# com.net
KiCad netlist of a schematic drawn in Altium Designer
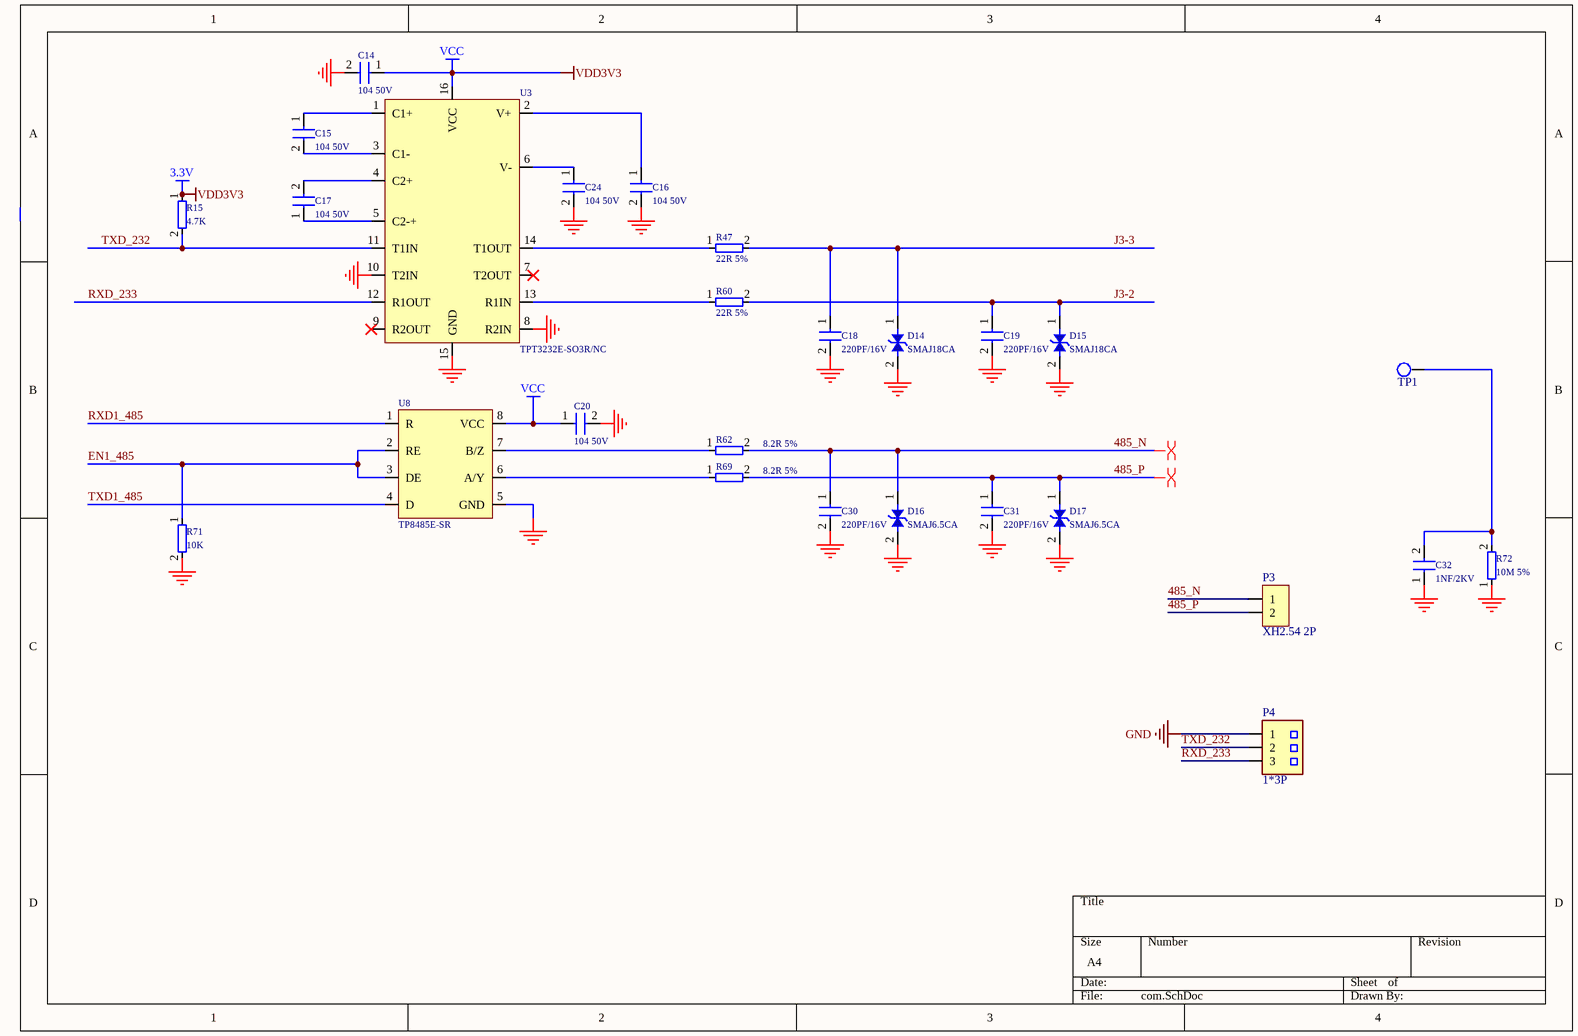
[diagram p0: com.SchDoc]

(export (version "E")
  (design (tool "Eeschema 10.0.6"))
  (components
    (comp (ref "C14") (value "104 50V") (footprint "0603C") (libsource (lib "*") (part "CAP")))
    (comp (ref "C15") (value "104 50V") (footprint "0603C") (libsource (lib "*") (part "CAP")))
    (comp (ref "C16") (value "104 50V") (footprint "0603C") (libsource (lib "*") (part "CAP")))
    (comp (ref "C17") (value "104 50V") (footprint "0603C") (libsource (lib "*") (part "CAP")))
    (comp (ref "C18") (value "220PF/16V") (footprint "0603C") (libsource (lib "*") (part "CAP")))
    (comp (ref "C19") (value "220PF/16V") (footprint "0603C") (libsource (lib "*") (part "CAP")))
    (comp (ref "C20") (value "104 50V") (footprint "0603C") (libsource (lib "*") (part "CAP")))
    (comp (ref "C24") (value "104 50V") (footprint "0603C") (libsource (lib "*") (part "CAP")))
    (comp (ref "C30") (value "220PF/16V") (footprint "0603C") (libsource (lib "*") (part "CAP")))
    (comp (ref "C31") (value "220PF/16V") (footprint "0603C") (libsource (lib "*") (part "CAP")))
    (comp (ref "C32") (value "1NF/2KV") (footprint "1206C") (libsource (lib "*") (part "CAP")))
    (comp (ref "D14") (value "SMAJ18CA") (footprint "SMA") (libsource (lib "*") (part "D_ESD")))
    (comp (ref "D15") (value "SMAJ18CA") (footprint "SMA") (libsource (lib "*") (part "D_ESD")))
    (comp (ref "D16") (value "SMAJ6.5CA") (footprint "SMA") (libsource (lib "*") (part "D_ESD")))
    (comp (ref "D17") (value "SMAJ6.5CA") (footprint "SMA") (libsource (lib "*") (part "D_ESD")))
    (comp (ref "P3")
      (value "XH2.54 2P")
      (footprint "SIP-2A")
      (description "XH2.54 2P 直插")
      (libsource (lib "XiaoyI") (part "SIP-2"))
    )
    (comp (ref "P4") (value "1*3P") (footprint "3X2.54MMZ2") (libsource (lib "PARK-N5 V1.0") (part "HDR1*3")))
    (comp (ref "R15") (value "4.7K") (footprint "0603R") (libsource (lib "*") (part "RES")))
    (comp (ref "R47") (value "22R 5%") (footprint "0603R") (libsource (lib "*") (part "RES")))
    (comp (ref "R60") (value "22R 5%") (footprint "0603R") (libsource (lib "*") (part "RES")))
    (comp (ref "R62") (value "8.2R 5%") (footprint "0603R") (libsource (lib "*") (part "RES")))
    (comp (ref "R69") (value "8.2R 5%") (footprint "0603R") (libsource (lib "*") (part "RES")))
    (comp (ref "R71") (value "10K") (footprint "0603R") (libsource (lib "*") (part "RES")))
    (comp (ref "R72") (value "10M 5%") (footprint "1206r") (libsource (lib "*") (part "RES")))
    (comp (ref "TP1") (value "TPS") (footprint "tpd") (libsource (lib "stm32") (part "TPS")))
    (comp (ref "U3")
      (value "TPT3232E-SO3R/NC")
      (footprint "SO-16Z")
      (libsource (lib "*") (part "TPT3232E-SO3R"))
    )
    (comp (ref "U8") (value "TP8485E-SR") (footprint "SO-8") (libsource (lib "*") (part "TP8485E-SR")))
  )
  (nets
    (net (code "1") (name "/485_N") (class "Default")
      (node (ref "C30") (pin "1") (pintype "passive"))
      (node (ref "D16") (pin "1") (pintype "passive"))
      (node (ref "P3") (pin "1") (pinfunction "1_1") (pintype "passive"))
      (node (ref "R62") (pin "2") (pinfunction "2_2") (pintype "passive"))
    )
    (net (code "2") (name "/485_P") (class "Default")
      (node (ref "C31") (pin "1") (pintype "passive"))
      (node (ref "D17") (pin "1") (pintype "passive"))
      (node (ref "P3") (pin "2") (pinfunction "2_2") (pintype "passive"))
      (node (ref "R69") (pin "2") (pinfunction "2_2") (pintype "passive"))
    )
    (net (code "3") (name "/EN1_485") (class "Default")
      (node (ref "R71") (pin "1") (pinfunction "1_1") (pintype "passive"))
      (node (ref "U8") (pin "2") (pinfunction "RE_2") (pintype "passive"))
      (node (ref "U8") (pin "3") (pinfunction "DE_3") (pintype "passive"))
    )
    (net (code "4") (name "/J3-2") (class "Default")
      (node (ref "C19") (pin "1") (pintype "passive"))
      (node (ref "D15") (pin "1") (pintype "passive"))
      (node (ref "R60") (pin "2") (pinfunction "2_2") (pintype "passive"))
    )
    (net (code "5") (name "/J3-3") (class "Default")
      (node (ref "C18") (pin "1") (pintype "passive"))
      (node (ref "D14") (pin "1") (pintype "passive"))
      (node (ref "R47") (pin "2") (pinfunction "2_2") (pintype "passive"))
    )
    (net (code "6") (name "/RXD1_485") (class "Default")
      (node (ref "U8") (pin "1") (pinfunction "R_1") (pintype "passive"))
    )
    (net (code "7") (name "/RXD_233") (class "Default")
      (node (ref "P4") (pin "3") (pinfunction "3_3") (pintype "passive"))
      (node (ref "U3") (pin "12") (pinfunction "R1OUT_12") (pintype "passive"))
    )
    (net (code "8") (name "/TXD1_485") (class "Default")
      (node (ref "U8") (pin "4") (pinfunction "D_4") (pintype "passive"))
    )
    (net (code "9") (name "/TXD_232") (class "Default")
      (node (ref "P4") (pin "2") (pinfunction "2_2") (pintype "passive"))
      (node (ref "R15") (pin "2") (pinfunction "2_2") (pintype "passive"))
      (node (ref "U3") (pin "11") (pinfunction "T1IN_11") (pintype "passive"))
    )
    (net (code "10") (name "3.3V") (class "Default")
      (node (ref "C14") (pin "1") (pintype "passive"))
      (node (ref "C20") (pin "1") (pintype "passive"))
      (node (ref "R15") (pin "1") (pinfunction "1_1") (pintype "passive"))
      (node (ref "U3") (pin "16") (pinfunction "VCC_16") (pintype "passive"))
      (node (ref "U8") (pin "8") (pinfunction "VCC_8") (pintype "passive"))
    )
    (net (code "11") (name "GND") (class "Default")
      (node (ref "C14") (pin "2") (pintype "passive"))
      (node (ref "C16") (pin "2") (pintype "passive"))
      (node (ref "C18") (pin "2") (pintype "passive"))
      (node (ref "C19") (pin "2") (pintype "passive"))
      (node (ref "C20") (pin "2") (pintype "passive"))
      (node (ref "C24") (pin "2") (pintype "passive"))
      (node (ref "C30") (pin "2") (pintype "passive"))
      (node (ref "C31") (pin "2") (pintype "passive"))
      (node (ref "C32") (pin "1") (pintype "passive"))
      (node (ref "D14") (pin "2") (pintype "passive"))
      (node (ref "D15") (pin "2") (pintype "passive"))
      (node (ref "D16") (pin "2") (pintype "passive"))
      (node (ref "D17") (pin "2") (pintype "passive"))
      (node (ref "P4") (pin "1") (pinfunction "1_1") (pintype "passive"))
      (node (ref "R71") (pin "2") (pinfunction "2_2") (pintype "passive"))
      (node (ref "R72") (pin "1") (pinfunction "1_1") (pintype "passive"))
      (node (ref "U3") (pin "10") (pinfunction "T2IN_10") (pintype "passive"))
      (node (ref "U3") (pin "15") (pinfunction "GND_15") (pintype "passive"))
      (node (ref "U3") (pin "8") (pinfunction "R2IN_8") (pintype "passive"))
      (node (ref "U8") (pin "5") (pinfunction "GND_5") (pintype "passive"))
    )
    (net (code "12") (name "Net-(C32-Pad2)") (class "Default")
      (node (ref "C32") (pin "2") (pintype "passive"))
      (node (ref "R72") (pin "2") (pinfunction "2_2") (pintype "passive"))
      (node (ref "TP1") (pin "1") (pinfunction "1_1") (pintype "passive"))
    )
    (net (code "13") (name "Net-(U3-C1+)") (class "Default")
      (node (ref "C15") (pin "1") (pintype "passive"))
      (node (ref "U3") (pin "1") (pinfunction "C1+_1") (pintype "passive"))
    )
    (net (code "14") (name "Net-(U3-C1-)") (class "Default")
      (node (ref "C15") (pin "2") (pintype "passive"))
      (node (ref "U3") (pin "3") (pinfunction "C1-_3") (pintype "passive"))
    )
    (net (code "15") (name "Net-(U3-C2+)") (class "Default")
      (node (ref "C17") (pin "2") (pintype "passive"))
      (node (ref "U3") (pin "4") (pinfunction "C2+_4") (pintype "passive"))
    )
    (net (code "16") (name "Net-(U3-C2-+)") (class "Default")
      (node (ref "C17") (pin "1") (pintype "passive"))
      (node (ref "U3") (pin "5") (pinfunction "C2-+_5") (pintype "passive"))
    )
    (net (code "17") (name "Net-(U3-R1IN)") (class "Default")
      (node (ref "R60") (pin "1") (pinfunction "1_1") (pintype "passive"))
      (node (ref "U3") (pin "13") (pinfunction "R1IN_13") (pintype "passive"))
    )
    (net (code "18") (name "Net-(U3-T1OUT)") (class "Default")
      (node (ref "R47") (pin "1") (pinfunction "1_1") (pintype "passive"))
      (node (ref "U3") (pin "14") (pinfunction "T1OUT_14") (pintype "passive"))
    )
    (net (code "19") (name "Net-(U3-V+)") (class "Default")
      (node (ref "C16") (pin "1") (pintype "passive"))
      (node (ref "U3") (pin "2") (pinfunction "V+_2") (pintype "passive"))
    )
    (net (code "20") (name "Net-(U3-V-)") (class "Default")
      (node (ref "C24") (pin "1") (pintype "passive"))
      (node (ref "U3") (pin "6") (pinfunction "V-_6") (pintype "passive"))
    )
    (net (code "21") (name "Net-(U8-A{slash}Y)") (class "Default")
      (node (ref "R69") (pin "1") (pinfunction "1_1") (pintype "passive"))
      (node (ref "U8") (pin "6") (pinfunction "A/Y_6") (pintype "passive"))
    )
    (net (code "22") (name "Net-(U8-B{slash}Z)") (class "Default")
      (node (ref "R62") (pin "1") (pinfunction "1_1") (pintype "passive"))
      (node (ref "U8") (pin "7") (pinfunction "B/Z_7") (pintype "passive"))
    )
    (net (code "23") (name "unconnected-(U3-R2OUT-Pad9)") (class "Default")
      (node (ref "U3") (pin "9") (pinfunction "R2OUT_9") (pintype "passive+no_connect"))
    )
    (net (code "24") (name "unconnected-(U3-T2OUT-Pad7)") (class "Default")
      (node (ref "U3") (pin "7") (pinfunction "T2OUT_7") (pintype "passive+no_connect"))
    )
  )
)
